# Shield_Schematic.net
KiCad netlist of a schematic drawn in EAGLE
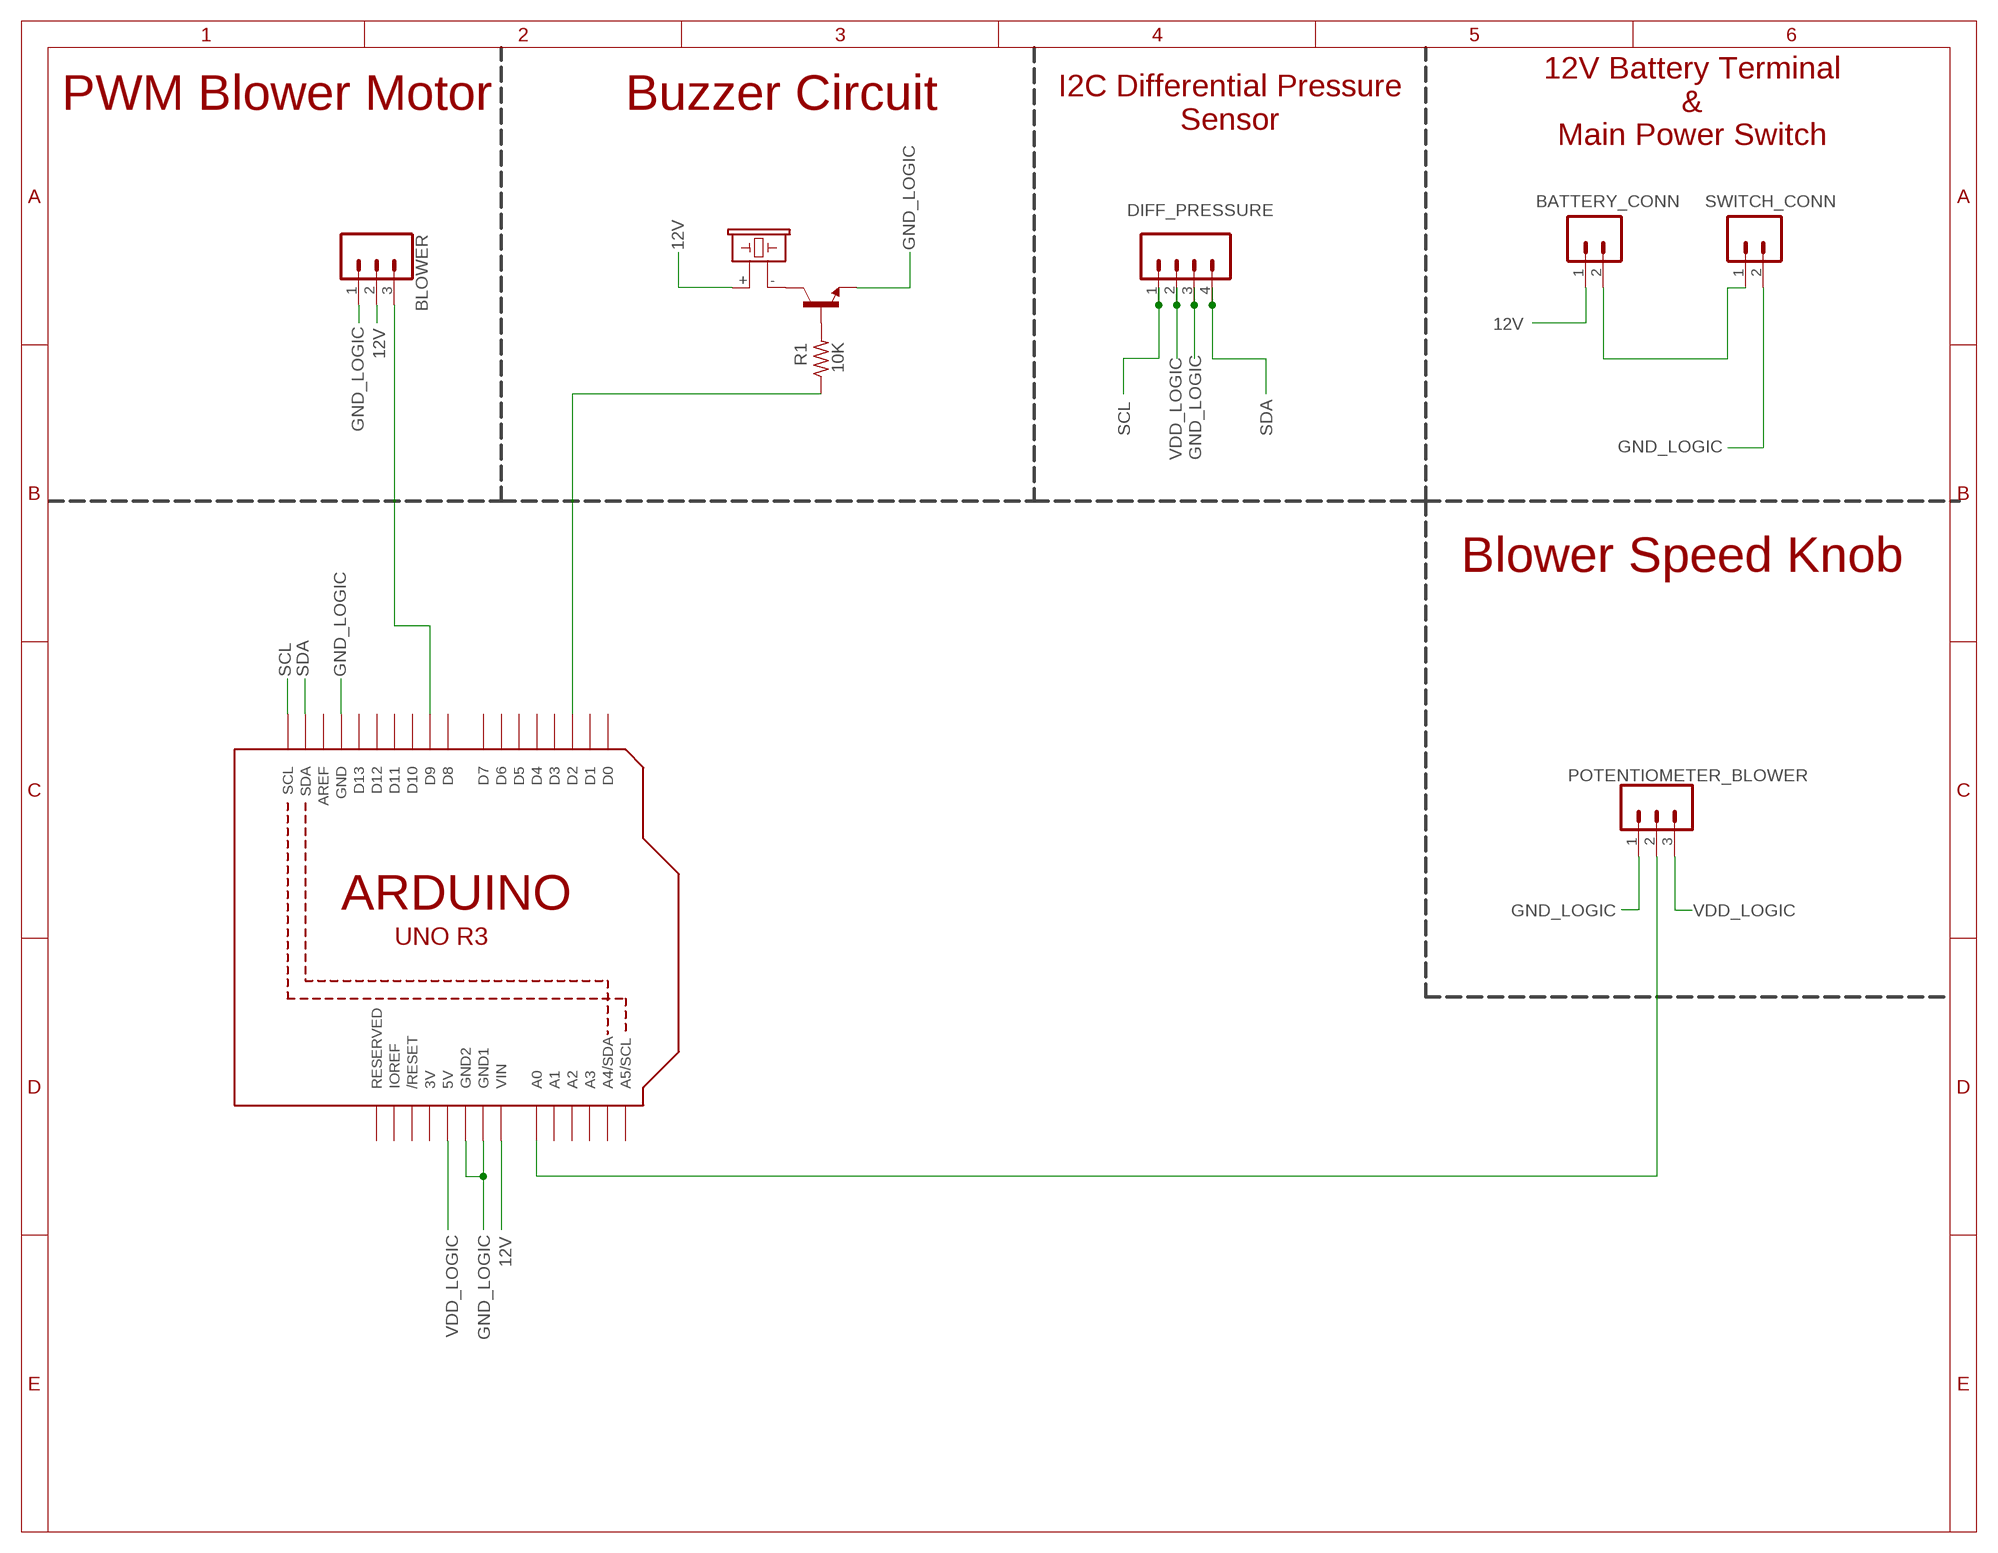
[diagram p0: schematic, sheet 1]

(export (version "E")
  (design (tool "Eeschema 10.0.6"))
  (components
    (comp (ref "BATTERY_CONN")
      (value "CONN_02PTH4")
      (footprint "eagle-import:1X02_XTRA_BIG")
      (libsource (lib "eagle-import") (part "CONN_02PTH4"))
    )
    (comp (ref "BLOWER")
      (value "CONN_03")
      (footprint "eagle-import:1X03")
      (libsource (lib "eagle-import") (part "CONN_03"))
    )
    (comp (ref "DIFF_PRESSURE")
      (value "CONN_04")
      (footprint "eagle-import:1X04")
      (libsource (lib "eagle-import") (part "CONN_04"))
    )
    (comp (ref "POTENTIOMETER_BLOWER")
      (value "CONN_03")
      (footprint "eagle-import:1X03")
      (libsource (lib "eagle-import") (part "CONN_03"))
    )
    (comp (ref "R1")
      (value "10K")
      (footprint "eagle-import:P0817V")
      (libsource (lib "eagle-import") (part "R-US_0817/7V"))
    )
    (comp (ref "SG1")
      (value "F/CM12P")
      (footprint "eagle-import:F_CM12P")
      (libsource (lib "eagle-import") (part "F/CM12P"))
    )
    (comp (ref "SWITCH_CONN")
      (value "CONN_02PTH4")
      (footprint "eagle-import:1X02_XTRA_BIG")
      (libsource (lib "eagle-import") (part "CONN_02PTH4"))
    )
    (comp (ref "T1")
      (value "2N5089")
      (footprint "eagle-import:TO92")
      (libsource (lib "eagle-import") (part "2N5089"))
    )
    (comp (ref "U1")
      (value "ARDUINOR3-DIMENSION")
      (footprint "eagle-import:ARDUINOR3")
      (libsource (lib "eagle-import") (part "ARDUINOR3-DIMENSION"))
    )
  )
  (nets
    (net (code "1") (name "/3V") (class "Default")
      (node (ref "U1") (pin "3V") (pinfunction "3V_3V") (pintype "power_in"))
    )
    (net (code "2") (name "/12V") (class "Default")
      (node (ref "BATTERY_CONN") (pin "1") (pinfunction "1_1") (pintype "passive"))
      (node (ref "BLOWER") (pin "2") (pinfunction "2_2") (pintype "passive"))
      (node (ref "SG1") (pin "+") (pinfunction "1_+") (pintype "passive"))
      (node (ref "U1") (pin "VIN") (pinfunction "VIN_VIN") (pintype "power_in"))
    )
    (net (code "3") (name "/GND_LOGIC") (class "Default")
      (node (ref "BLOWER") (pin "1") (pinfunction "1_1") (pintype "passive"))
      (node (ref "DIFF_PRESSURE") (pin "3") (pinfunction "3_3") (pintype "passive"))
      (node (ref "POTENTIOMETER_BLOWER") (pin "1") (pinfunction "1_1") (pintype "passive"))
      (node (ref "SWITCH_CONN") (pin "2") (pinfunction "2_2") (pintype "passive"))
      (node (ref "T1") (pin "3") (pinfunction "E_3") (pintype "passive"))
      (node (ref "U1") (pin "GND") (pinfunction "GND_GND") (pintype "power_in"))
      (node (ref "U1") (pin "GND1") (pinfunction "GND1_GND1") (pintype "power_in"))
      (node (ref "U1") (pin "GND2") (pinfunction "GND2_GND2") (pintype "power_in"))
    )
    (net (code "4") (name "/SCL") (class "Default")
      (node (ref "DIFF_PRESSURE") (pin "1") (pinfunction "1_1") (pintype "passive"))
      (node (ref "U1") (pin "SCL") (pinfunction "SCL_SCL") (pintype "bidirectional"))
    )
    (net (code "5") (name "/SDA") (class "Default")
      (node (ref "DIFF_PRESSURE") (pin "4") (pinfunction "4_4") (pintype "passive"))
      (node (ref "U1") (pin "SDA") (pinfunction "SDA_SDA") (pintype "bidirectional"))
    )
    (net (code "6") (name "/VDD_LOGIC") (class "Default")
      (node (ref "DIFF_PRESSURE") (pin "2") (pinfunction "2_2") (pintype "passive"))
      (node (ref "POTENTIOMETER_BLOWER") (pin "3") (pinfunction "3_3") (pintype "passive"))
      (node (ref "U1") (pin "5V") (pinfunction "5V_5V") (pintype "power_in"))
    )
    (net (code "7") (name "Net-(BATTERY_CONN-Pad2)") (class "Default")
      (node (ref "BATTERY_CONN") (pin "2") (pinfunction "2_2") (pintype "passive"))
      (node (ref "SWITCH_CONN") (pin "1") (pinfunction "1_1") (pintype "passive"))
    )
    (net (code "8") (name "Net-(BLOWER-Pad3)") (class "Default")
      (node (ref "BLOWER") (pin "3") (pinfunction "3_3") (pintype "passive"))
      (node (ref "U1") (pin "D9") (pinfunction "D9_D9") (pintype "bidirectional"))
    )
    (net (code "9") (name "Net-(POTENTIOMETER_BLOWER-Pad2)") (class "Default")
      (node (ref "POTENTIOMETER_BLOWER") (pin "2") (pinfunction "2_2") (pintype "passive"))
      (node (ref "U1") (pin "A0") (pinfunction "A0_A0") (pintype "bidirectional"))
    )
    (net (code "10") (name "Net-(R1-Pad1)") (class "Default")
      (node (ref "R1") (pin "1") (pinfunction "1_1") (pintype "passive"))
      (node (ref "U1") (pin "D2") (pinfunction "D2_D2") (pintype "bidirectional"))
    )
    (net (code "11") (name "Net-(SG1-2)") (class "Default")
      (node (ref "SG1") (pin "-") (pinfunction "2_-") (pintype "passive"))
      (node (ref "T1") (pin "1") (pinfunction "C_1") (pintype "passive"))
    )
    (net (code "12") (name "Net-(T1-B)") (class "Default")
      (node (ref "R1") (pin "2") (pinfunction "2_2") (pintype "passive"))
      (node (ref "T1") (pin "2") (pinfunction "B_2") (pintype "passive"))
    )
    (net (code "13") (name "unconnected-(U1-A4{slash}SDA-PadA4)") (class "Default")
      (node (ref "U1") (pin "A4") (pinfunction "A4/SDA_A4") (pintype "bidirectional"))
    )
    (net (code "14") (name "unconnected-(U1-A5{slash}SCL-PadA5)") (class "Default")
      (node (ref "U1") (pin "A5") (pinfunction "A5/SCL_A5") (pintype "bidirectional"))
    )
    (net (code "15") (name "unconnected-(U1-PadA1)") (class "Default")
      (node (ref "U1") (pin "A1") (pinfunction "A1_A1") (pintype "bidirectional"))
    )
    (net (code "16") (name "unconnected-(U1-PadA2)") (class "Default")
      (node (ref "U1") (pin "A2") (pinfunction "A2_A2") (pintype "bidirectional"))
    )
    (net (code "17") (name "unconnected-(U1-PadA3)") (class "Default")
      (node (ref "U1") (pin "A3") (pinfunction "A3_A3") (pintype "bidirectional"))
    )
    (net (code "18") (name "unconnected-(U1-PadAREF)") (class "Default")
      (node (ref "U1") (pin "AREF") (pinfunction "AREF_AREF") (pintype "bidirectional"))
    )
    (net (code "19") (name "unconnected-(U1-PadD0)") (class "Default")
      (node (ref "U1") (pin "D0") (pinfunction "D0_D0") (pintype "bidirectional"))
    )
    (net (code "20") (name "unconnected-(U1-PadD1)") (class "Default")
      (node (ref "U1") (pin "D1") (pinfunction "D1_D1") (pintype "bidirectional"))
    )
    (net (code "21") (name "unconnected-(U1-PadD3)") (class "Default")
      (node (ref "U1") (pin "D3") (pinfunction "D3_D3") (pintype "bidirectional"))
    )
    (net (code "22") (name "unconnected-(U1-PadD4)") (class "Default")
      (node (ref "U1") (pin "D4") (pinfunction "D4_D4") (pintype "bidirectional"))
    )
    (net (code "23") (name "unconnected-(U1-PadD5)") (class "Default")
      (node (ref "U1") (pin "D5") (pinfunction "D5_D5") (pintype "bidirectional"))
    )
    (net (code "24") (name "unconnected-(U1-PadD6)") (class "Default")
      (node (ref "U1") (pin "D6") (pinfunction "D6_D6") (pintype "bidirectional"))
    )
    (net (code "25") (name "unconnected-(U1-PadD7)") (class "Default")
      (node (ref "U1") (pin "D7") (pinfunction "D7_D7") (pintype "bidirectional"))
    )
    (net (code "26") (name "unconnected-(U1-PadD8)") (class "Default")
      (node (ref "U1") (pin "D8") (pinfunction "D8_D8") (pintype "bidirectional"))
    )
    (net (code "27") (name "unconnected-(U1-PadD10)") (class "Default")
      (node (ref "U1") (pin "D10") (pinfunction "D10_D10") (pintype "bidirectional"))
    )
    (net (code "28") (name "unconnected-(U1-PadD11)") (class "Default")
      (node (ref "U1") (pin "D11") (pinfunction "D11_D11") (pintype "bidirectional"))
    )
    (net (code "29") (name "unconnected-(U1-PadD12)") (class "Default")
      (node (ref "U1") (pin "D12") (pinfunction "D12_D12") (pintype "bidirectional"))
    )
    (net (code "30") (name "unconnected-(U1-PadD13)") (class "Default")
      (node (ref "U1") (pin "D13") (pinfunction "D13_D13") (pintype "bidirectional"))
    )
    (net (code "31") (name "unconnected-(U1-PadIOREF)") (class "Default")
      (node (ref "U1") (pin "IOREF") (pinfunction "IOREF_IOREF") (pintype "output"))
    )
    (net (code "32") (name "unconnected-(U1-PadRESERVED)") (class "Default")
      (node (ref "U1") (pin "RESERVED") (pinfunction "RESERVED_RESERVED") (pintype "no_connect"))
    )
    (net (code "33") (name "unconnected-(U1-{slash}RESET-PadRESET)") (class "Default")
      (node (ref "U1") (pin "RESET") (pinfunction "/RESET_RESET") (pintype "bidirectional"))
    )
  )
)
